# deel2.net
KiCad netlist of a schematic drawn in Altium Designer
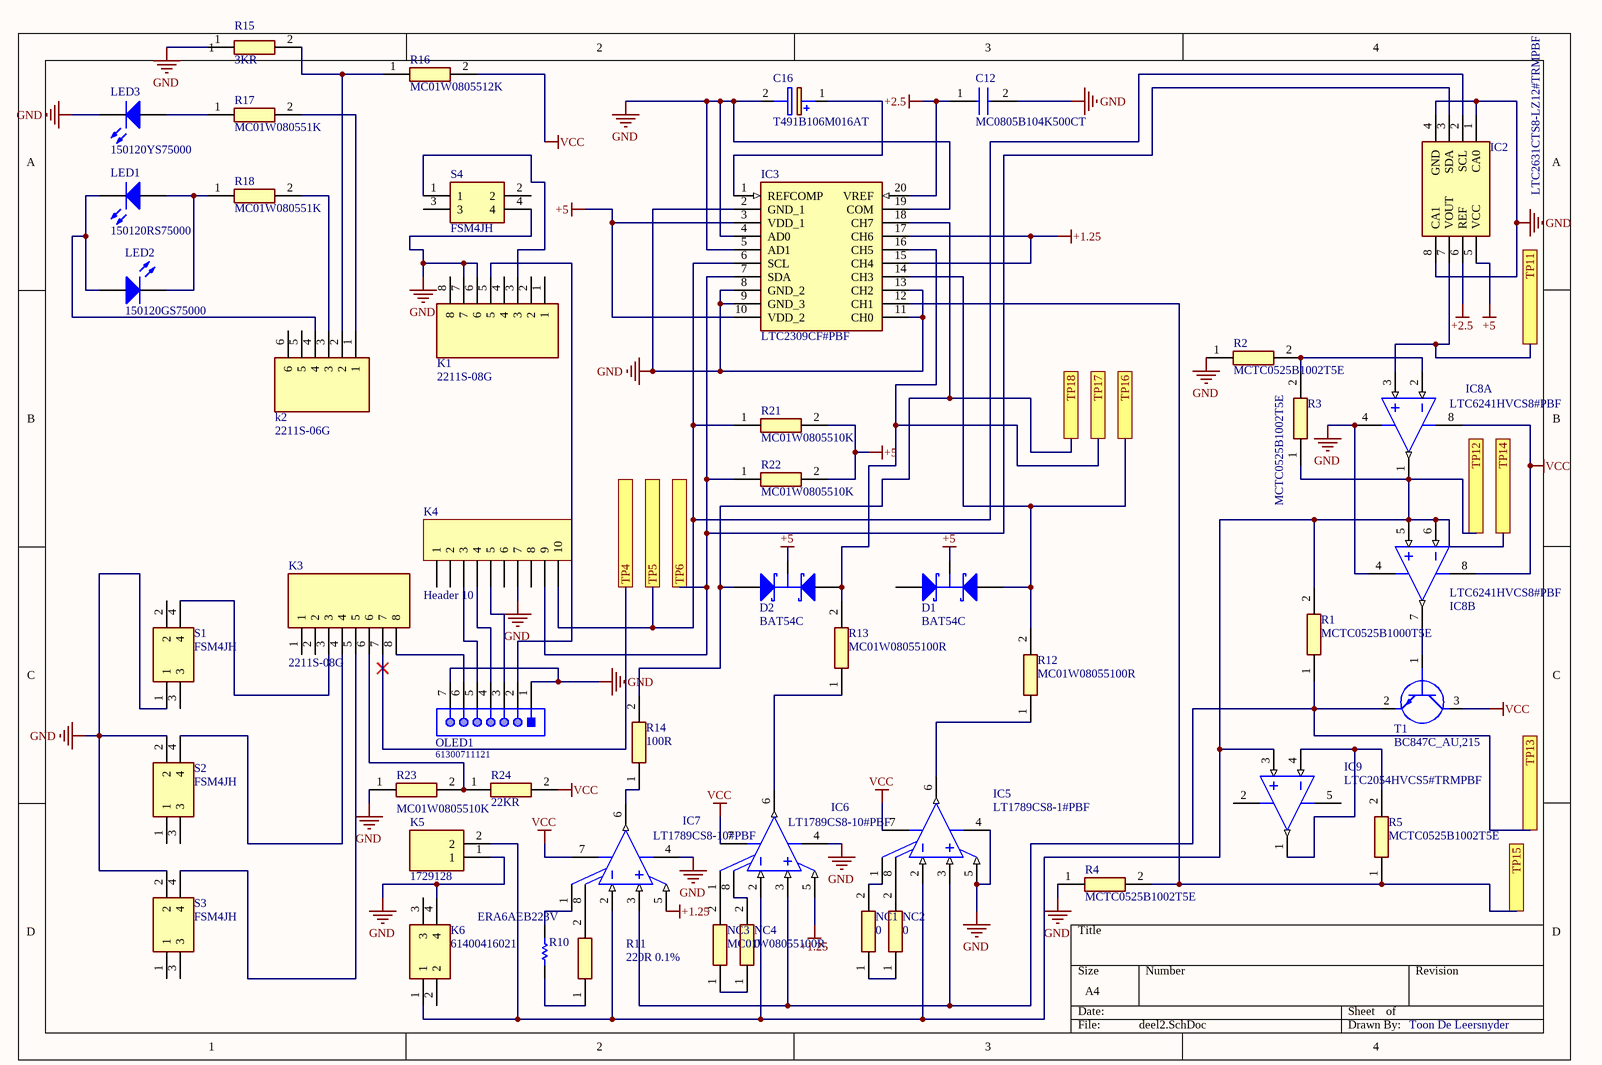
[diagram p0: deel2.SchDoc]

(export (version "E")
  (design (tool "Eeschema 10.0.6"))
  (components
    (comp (ref "C12")
      (value "MC0805B104K500CT")
      (footprint "SamacSys:CAPC2012X90N")
      (description "Capacitor")
      (libsource (lib "SamacSys") (part "MC0805B104K500CT"))
    )
    (comp (ref "C16")
      (value "T491B106M016AT")
      (footprint "SamacSys:CAPPM3528X210N")
      (description "Capacitor Polarised")
      (fields (field (name "MOUSER PART NUMBER") "80-T491B106M016"))
      (libsource (lib "SamacSys") (part "T491B106M016AT"))
    )
    (comp (ref "D1")
      (value "BAT54C")
      (footprint "NXP-SOT23-3_V")
      (description "Schottky Barrier Diode, 30 V, 2 uA, -55 to 150 degC, 3-Pin SOT23, RoHS, Tape and Reel")
      (fields (field (name "MANUFACTURER") "NXP Semiconductors"))
      (libsource (lib "Altium Content Vault") (part "NXP-DSKY_A1A2K3-3"))
    )
    (comp (ref "D2")
      (value "BAT54C")
      (footprint "NXP-SOT23-3_V")
      (description "Schottky Barrier Diode, 30 V, 2 uA, -55 to 150 degC, 3-Pin SOT23, RoHS, Tape and Reel")
      (fields (field (name "MANUFACTURER") "NXP Semiconductors"))
      (libsource (lib "Altium Content Vault") (part "NXP-DSKY_A1A2K3-3"))
    )
    (comp (ref "IC2")
      (value "LTC2631CTS8-LZ12#TRMPBF")
      (footprint "SamacSys:SOT65P280X100-8N")
      (description "Integrated Circuit")
      (fields (field (name "MOUSER PART NUMBER") "584-2631CTS8LZ12TMPF"))
      (libsource (lib "SamacSys") (part "LTC2631CTS8-LZ12#TRMPBF"))
    )
    (comp (ref "IC3")
      (value "LTC2309CF#PBF")
      (footprint "SamacSys:SOP65P640X110-20N")
      (description "Integrated Circuit")
      (fields (field (name "MOUSER PART NUMBER") "584-LTC2309CF#PBF"))
      (libsource (lib "SamacSys") (part "LTC2309CF#PBF"))
    )
    (comp (ref "IC5")
      (value "LT1789CS8-1#PBF")
      (footprint "LT-S8-8_N")
      (fields
        (field (name "MANUFACTURER") "Linear Technology")
        (field (name "LINEAR TECHNOLOGY PART NUMBER") "LT1789-1")
      )
      (libsource (lib "Altium Content Vault") (part "LT-LT1789-1-S8-8"))
    )
    (comp (ref "IC6")
      (value "LT1789CS8-10#PBF")
      (footprint "LT-S8-8_N")
      (fields
        (field (name "MANUFACTURER") "Linear Technology")
        (field (name "LINEAR TECHNOLOGY PART NUMBER") "LT1789-10")
      )
      (libsource (lib "Altium Content Vault") (part "LT-LT1789-10-S8-8"))
    )
    (comp (ref "IC7")
      (value "LT1789CS8-10#PBF")
      (footprint "LT-S8-8_N")
      (fields
        (field (name "MANUFACTURER") "Linear Technology")
        (field (name "LINEAR TECHNOLOGY PART NUMBER") "LT1789-10")
      )
      (libsource (lib "Altium Content Vault") (part "LT-LT1789-10-S8-8"))
    )
    (comp (ref "IC8")
      (value "LTC6241HVCS8#PBF")
      (footprint "LT-S8-8_M")
      (fields
        (field (name "LINEAR TECHNOLOGY PART NUMBER") "LTC6241HV")
        (field (name "MANUFACTURER") "Linear Technology")
      )
      (libsource (lib "Altium Content Vault") (part "LT-LTC6241HV-S8-8"))
    )
    (comp (ref "IC9")
      (value "LTC2054HVCS5#TRMPBF")
      (footprint "LT-S5-5-TSOT-23_N")
      (fields
        (field (name "LINEAR TECHNOLOGY PART NUMBER") "LTC2054HV")
        (field (name "MANUFACTURER") "Linear Technology")
      )
      (libsource (lib "Altium Content Vault") (part "LT-LT1395-LT18XX-LTC20XX-5"))
    )
    (comp (ref "K1")
      (value "2211S-08G")
      (footprint "SamacSys:HDRV8W64P0X254_1X8_2032X254X874P")
      (description "Connector")
      (libsource (lib "") (part "2211S-08G_1"))
    )
    (comp (ref "k2")
      (value "2211S-06G")
      (footprint "SamacSys:HDRV6W64P0X254_1X6_1524X254X1774P")
      (description "Connector")
      (libsource (lib "SamacSys") (part "2211S-06G"))
    )
    (comp (ref "K3")
      (value "2211S-08G")
      (footprint "SamacSys:HDRV8W64P0X254_1X8_2032X254X874P")
      (description "Connector")
      (libsource (lib "SamacSys") (part "2211S-08G"))
    )
    (comp (ref "K4")
      (value "Header 10")
      (footprint "HDR1X10")
      (description "Header, 10-Pin")
      (fields (field (name "PUBLISHER") "Altium Limited"))
      (libsource (lib "Miscellaneous Connectors") (part "Header 10"))
    )
    (comp (ref "K5")
      (value "1729128")
      (footprint "SamacSys:HDRV2W110P0X508_1X2_1016X810X1000P")
      (description "Connector")
      (fields (field (name "MOUSER PART NUMBER") "651-1729128"))
      (libsource (lib "SamacSys") (part "1729128"))
    )
    (comp (ref "K6")
      (value "61400416021")
      (footprint "SamacSys:USB-2.0-TYPE-A")
      (description "Connector")
      (fields (field (name "MOUSER PART NUMBER") "710-61400416021"))
      (libsource (lib "SamacSys") (part "61400416021"))
    )
    (comp (ref "LED1")
      (value "150120RS75000")
      (footprint "1206_A")
      (description "SMD mono-color Chip LED, WL-SMCW, Red")
      (fields (field (name "MANUFACTURER") "Wuerth Elektronik"))
      (libsource (lib "Altium Content Vault") (part "WE-LED_K1A2-2"))
    )
    (comp (ref "LED2")
      (value "150120GS75000")
      (footprint "1206_A")
      (description "SMD mono-color Chip LED, WL-SMCW, Green")
      (fields (field (name "MANUFACTURER") "Wuerth Elektronik"))
      (libsource (lib "Altium Content Vault") (part "WE-LED_K1A2-2"))
    )
    (comp (ref "LED3")
      (value "150120YS75000")
      (footprint "1206_A")
      (description "SMD mono-color Chip LED, WL-SMCW, Yellow")
      (fields (field (name "MANUFACTURER") "Wuerth Elektronik"))
      (libsource (lib "Altium Content Vault") (part "WE-LED_K1A2-2"))
    )
    (comp (ref "NC1")
      (value "0")
      (footprint "SamacSys:RESC2014X65N")
      (description "Resistor")
      (fields (field (name "MANUFACTURER_PART_NUMBER") "MC01W08055100R"))
      (libsource (lib "SamacSys") (part "MC01W08055100R"))
    )
    (comp (ref "NC2")
      (value "0")
      (footprint "SamacSys:RESC2014X65N")
      (description "Resistor")
      (fields (field (name "MANUFACTURER_PART_NUMBER") "MC01W08055100R"))
      (libsource (lib "SamacSys") (part "MC01W08055100R"))
    )
    (comp (ref "NC3")
      (value "MC01W08055100R")
      (footprint "SamacSys:RESC2014X65N")
      (description "Resistor")
      (libsource (lib "SamacSys") (part "MC01W08055100R"))
    )
    (comp (ref "NC4")
      (value "0")
      (footprint "SamacSys:RESC2014X65N")
      (description "Resistor")
      (fields (field (name "MANUFACTURER_PART_NUMBER") "MC01W08055100R"))
      (libsource (lib "SamacSys") (part "MC01W08055100R"))
    )
    (comp (ref "OLED1")
      (value "61300711121")
      (footprint "61300711121")
      (description "THT Vertical Pin Header WR-PHD, Pitch 2.54 mm, Single Row, 7 pins")
      (fields (field (name "MANUFACTURER") "Wurth Elektronik") (field (name "PUBLISHER") "WurthElektronik"))
      (libsource (lib "Altium Content Vault") (part "WE-CN-1P-M-R7"))
    )
    (comp (ref "R1")
      (value "MCTC0525B1000T5E")
      (footprint "SamacSys:RESC2012X65N")
      (description "Resistor")
      (libsource (lib "SamacSys") (part "MCTC0525B1000T5E"))
    )
    (comp (ref "R2")
      (value "MCTC0525B1002T5E")
      (footprint "SamacSys:RESC2012X65N")
      (description "Resistor")
      (libsource (lib "SamacSys") (part "MCTC0525B1002T5E"))
    )
    (comp (ref "R3")
      (value "MCTC0525B1002T5E")
      (footprint "SamacSys:RESC2012X65N")
      (description "Resistor")
      (libsource (lib "") (part "MCTC0525B1002T5E_1"))
    )
    (comp (ref "R4")
      (value "MCTC0525B1002T5E")
      (footprint "SamacSys:RESC2012X65N")
      (description "Resistor")
      (libsource (lib "SamacSys") (part "MCTC0525B1002T5E"))
    )
    (comp (ref "R5")
      (value "MCTC0525B1002T5E")
      (footprint "SamacSys:RESC2012X65N")
      (description "Resistor")
      (libsource (lib "") (part "MCTC0525B1002T5E_1"))
    )
    (comp (ref "R10")
      (value "ERA6AEB223V")
      (footprint "RESC2013X60X40ML20T25")
      (fields (field (name "MANUFACTURER") "Panasonic"))
      (libsource (lib "Altium Content Vault") (part "RES"))
    )
    (comp (ref "R11")
      (value "220R 0.1%")
      (footprint "SamacSys:RESC2014X65N")
      (description "Resistor")
      (fields (field (name "MANUFACTURER_PART_NUMBER") "MC01W08055100R"))
      (libsource (lib "SamacSys") (part "MC01W08055100R"))
    )
    (comp (ref "R12")
      (value "MC01W08055100R")
      (footprint "SamacSys:RESC2014X65N")
      (description "Resistor")
      (libsource (lib "SamacSys") (part "MC01W08055100R"))
    )
    (comp (ref "R13")
      (value "MC01W08055100R")
      (footprint "SamacSys:RESC2014X65N")
      (description "Resistor")
      (libsource (lib "SamacSys") (part "MC01W08055100R"))
    )
    (comp (ref "R14")
      (value "100R")
      (footprint "SamacSys:RESC2014X65N")
      (description "Resistor")
      (fields (field (name "MANUFACTURER_PART_NUMBER") "MC01W08055100R"))
      (libsource (lib "SamacSys") (part "MC01W08055100R"))
    )
    (comp (ref "R15")
      (value "3KR")
      (footprint "SamacSys:RESC2014X65N")
      (description "Resistor")
      (fields (field (name "MANUFACTURER_PART_NUMBER") "MC01W08055100R"))
      (libsource (lib "") (part "MC01W08055100R_1"))
    )
    (comp (ref "R16")
      (value "MC01W0805512K")
      (footprint "SamacSys:RESC2014X65N")
      (description "Resistor")
      (libsource (lib "SamacSys") (part "MC01W0805512K"))
    )
    (comp (ref "R17")
      (value "MC01W080551K")
      (footprint "SamacSys:RESC2014X65N")
      (description "Resistor")
      (libsource (lib "SamacSys") (part "MC01W080551K"))
    )
    (comp (ref "R18")
      (value "MC01W080551K")
      (footprint "SamacSys:RESC2014X65N")
      (description "Resistor")
      (libsource (lib "SamacSys") (part "MC01W080551K"))
    )
    (comp (ref "R21")
      (value "MC01W0805510K")
      (footprint "SamacSys:RESC2014X65N")
      (description "Resistor")
      (libsource (lib "SamacSys") (part "MC01W0805510K"))
    )
    (comp (ref "R22")
      (value "MC01W0805510K")
      (footprint "SamacSys:RESC2014X65N")
      (description "Resistor")
      (libsource (lib "SamacSys") (part "MC01W0805510K"))
    )
    (comp (ref "R23")
      (value "MC01W0805510K")
      (footprint "SamacSys:RESC2014X65N")
      (description "Resistor")
      (libsource (lib "SamacSys") (part "MC01W0805510K"))
    )
    (comp (ref "R24")
      (value "22KR")
      (footprint "SamacSys:RESC2014X65N")
      (description "Resistor")
      (fields (field (name "MANUFACTURER_PART_NUMBER") "MC01W08055100R"))
      (libsource (lib "") (part "MC01W08055100R_1"))
    )
    (comp (ref "S1")
      (value "FSM4JH")
      (footprint "SamacSys:FSM4JH")
      (description "Switch")
      (fields (field (name "MOUSER PART NUMBER") "506-FSM4JH"))
      (libsource (lib "SamacSys") (part "FSM4JH"))
    )
    (comp (ref "S2")
      (value "FSM4JH")
      (footprint "SamacSys:FSM4JH")
      (description "Switch")
      (fields (field (name "MOUSER PART NUMBER") "506-FSM4JH"))
      (libsource (lib "SamacSys") (part "FSM4JH"))
    )
    (comp (ref "S3")
      (value "FSM4JH")
      (footprint "SamacSys:FSM4JH")
      (description "Switch")
      (fields (field (name "MOUSER PART NUMBER") "506-FSM4JH"))
      (libsource (lib "SamacSys") (part "FSM4JH"))
    )
    (comp (ref "S4")
      (value "FSM4JH")
      (footprint "SamacSys:FSM4JH")
      (description "Switch")
      (fields (field (name "MOUSER PART NUMBER") "506-FSM4JH"))
      (libsource (lib "") (part "FSM4JH_1"))
    )
    (comp (ref "T1")
      (value "BC847C_AU,215")
      (footprint "SamacSys:SOT95P230X110-3N")
      (description "Transistor BJT NPN")
      (fields (field (name "MANUFACTURER_PART_NUMBER") "BC847C/AU,215"))
      (libsource (lib "SamacSys") (part "BC847C_AU,215"))
    )
  )
  (nets
    (net (code "1") (name "+1.25") (class "Default")
      (node (ref "IC3") (pin "15") (pinfunction "CH4_15") (pintype "passive"))
      (node (ref "IC3") (pin "17") (pinfunction "CH6_17") (pintype "passive"))
      (node (ref "IC6") (pin "5") (pinfunction "REF_5") (pintype "input"))
      (node (ref "IC7") (pin "5") (pinfunction "REF_5") (pintype "input"))
    )
    (net (code "2") (name "+2.5") (class "Default")
      (node (ref "C12") (pin "1") (pinfunction "1_1") (pintype "passive"))
      (node (ref "IC2") (pin "6") (pinfunction "REF_6") (pintype "passive"))
      (node (ref "IC3") (pin "20") (pinfunction "VREF_20") (pintype "input"))
    )
    (net (code "3") (name "+5") (class "Default")
      (node (ref "D1") (pin "3") (pinfunction "K_3") (pintype "passive"))
      (node (ref "D2") (pin "3") (pinfunction "K_3") (pintype "passive"))
      (node (ref "IC2") (pin "5") (pinfunction "VCC_5") (pintype "passive"))
      (node (ref "IC3") (pin "10") (pinfunction "VDD_2_10") (pintype "power_in"))
      (node (ref "IC3") (pin "3") (pinfunction "VDD_1_3") (pintype "power_in"))
      (node (ref "R21") (pin "2") (pinfunction "2_2") (pintype "passive"))
      (node (ref "R22") (pin "2") (pinfunction "2_2") (pintype "passive"))
    )
    (net (code "4") (name "/TP4") (class "Default")
      (node (ref "K3") (pin "7") (pinfunction "7_7") (pintype "passive"))
    )
    (net (code "5") (name "/TP5") (class "Default")
      (node (ref "IC2") (pin "2") (pinfunction "SCL_2") (pintype "passive"))
      (node (ref "IC3") (pin "6") (pinfunction "SCL_6") (pintype "passive"))
      (node (ref "K4") (pin "10") (pinfunction "10_10") (pintype "passive"))
      (node (ref "R21") (pin "1") (pinfunction "1_1") (pintype "passive"))
    )
    (net (code "6") (name "/TP6") (class "Default")
      (node (ref "IC2") (pin "3") (pinfunction "SDA_3") (pintype "passive"))
      (node (ref "IC3") (pin "7") (pinfunction "SDA_7") (pintype "passive"))
      (node (ref "K4") (pin "9") (pinfunction "9_9") (pintype "passive"))
      (node (ref "R22") (pin "1") (pinfunction "1_1") (pintype "passive"))
    )
    (net (code "7") (name "/TP11") (class "Default")
      (node (ref "IC2") (pin "7") (pinfunction "VOUT_7") (pintype "passive"))
      (node (ref "IC8") (pin "3") (pinfunction "+IN_A_3") (pintype "input"))
    )
    (net (code "8") (name "/TP12") (class "Default")
      (node (ref "IC5") (pin "2") (pinfunction "-IN_2") (pintype "input"))
      (node (ref "IC6") (pin "2") (pinfunction "-IN_2") (pintype "input"))
      (node (ref "IC7") (pin "2") (pinfunction "-IN_2") (pintype "input"))
      (node (ref "IC8") (pin "1") (pinfunction "OUT_A_1") (pintype "output"))
      (node (ref "IC8") (pin "5") (pinfunction "+IN_B_5") (pintype "input"))
      (node (ref "IC8") (pin "6") (pinfunction "-IN_B_6") (pintype "input"))
      (node (ref "IC9") (pin "3") (pinfunction "+IN_3") (pintype "input"))
      (node (ref "K5") (pin "2") (pinfunction "2_2") (pintype "passive"))
      (node (ref "K6") (pin "1") (pinfunction "1_1") (pintype "passive"))
      (node (ref "R1") (pin "2") (pinfunction "2_2") (pintype "passive"))
      (node (ref "R3") (pin "1") (pinfunction "1_1") (pintype "passive"))
    )
    (net (code "9") (name "/TP13") (class "Default")
      (node (ref "IC5") (pin "3") (pinfunction "+IN_3") (pintype "input"))
      (node (ref "IC6") (pin "3") (pinfunction "+IN_3") (pintype "input"))
      (node (ref "IC7") (pin "3") (pinfunction "+IN_3") (pintype "input"))
      (node (ref "R1") (pin "1") (pinfunction "1_1") (pintype "passive"))
      (node (ref "T1") (pin "2") (pinfunction "E_2") (pintype "passive"))
    )
    (net (code "10") (name "/TP15") (class "Default")
      (node (ref "IC3") (pin "12") (pinfunction "CH1_12") (pintype "passive"))
      (node (ref "R4") (pin "2") (pinfunction "2_2") (pintype "passive"))
      (node (ref "R5") (pin "1") (pinfunction "1_1") (pintype "passive"))
    )
    (net (code "11") (name "/TP16") (class "Default")
      (node (ref "D1") (pin "2") (pinfunction "A_2") (pintype "passive"))
      (node (ref "IC3") (pin "14") (pinfunction "CH3_14") (pintype "passive"))
      (node (ref "R12") (pin "2") (pinfunction "2_2") (pintype "passive"))
    )
    (net (code "12") (name "/TP17") (class "Default")
      (node (ref "D2") (pin "2") (pinfunction "A_2") (pintype "passive"))
      (node (ref "IC3") (pin "16") (pinfunction "CH5_16") (pintype "passive"))
      (node (ref "R13") (pin "2") (pinfunction "2_2") (pintype "passive"))
    )
    (net (code "13") (name "/TP18") (class "Default")
      (node (ref "D2") (pin "1") (pinfunction "A_1") (pintype "passive"))
      (node (ref "IC3") (pin "18") (pinfunction "CH7_18") (pintype "passive"))
      (node (ref "R14") (pin "2") (pinfunction "2_2") (pintype "passive"))
    )
    (net (code "14") (name "GND") (class "Default")
      (node (ref "C12") (pin "2") (pinfunction "2_2") (pintype "passive"))
      (node (ref "C16") (pin "2") (pinfunction "-_2") (pintype "passive"))
      (node (ref "IC2") (pin "1") (pinfunction "CA0_1") (pintype "passive"))
      (node (ref "IC2") (pin "4") (pinfunction "GND_4") (pintype "passive"))
      (node (ref "IC2") (pin "8") (pinfunction "CA1_8") (pintype "passive"))
      (node (ref "IC3") (pin "11") (pinfunction "CH0_11") (pintype "passive"))
      (node (ref "IC3") (pin "13") (pinfunction "CH2_13") (pintype "passive"))
      (node (ref "IC3") (pin "19") (pinfunction "COM_19") (pintype "passive"))
      (node (ref "IC3") (pin "2") (pinfunction "GND_1_2") (pintype "power_in"))
      (node (ref "IC3") (pin "4") (pinfunction "AD0_4") (pintype "passive"))
      (node (ref "IC3") (pin "5") (pinfunction "AD1_5") (pintype "passive"))
      (node (ref "IC3") (pin "8") (pinfunction "GND_2_8") (pintype "power_in"))
      (node (ref "IC3") (pin "9") (pinfunction "GND_3_9") (pintype "power_in"))
      (node (ref "IC5") (pin "4") (pinfunction "-VS_4") (pintype "power_in"))
      (node (ref "IC5") (pin "5") (pinfunction "REF_5") (pintype "input"))
      (node (ref "IC6") (pin "4") (pinfunction "-VS_4") (pintype "power_in"))
      (node (ref "IC7") (pin "4") (pinfunction "-VS_4") (pintype "power_in"))
      (node (ref "IC8") (pin "4") (pinfunction "V-_4") (pintype "power_in"))
      (node (ref "K1") (pin "6") (pinfunction "6_6") (pintype "passive"))
      (node (ref "K1") (pin "7") (pinfunction "7_7") (pintype "passive"))
      (node (ref "K4") (pin "7") (pinfunction "7_7") (pintype "passive"))
      (node (ref "K5") (pin "1") (pinfunction "1_1") (pintype "passive"))
      (node (ref "K6") (pin "4") (pinfunction "4_4") (pintype "passive"))
      (node (ref "LED3") (pin "1") (pinfunction "K_1") (pintype "passive"))
      (node (ref "OLED1") (pin "1") (pinfunction "1_1") (pintype "passive"))
      (node (ref "OLED1") (pin "7") (pinfunction "7_7") (pintype "passive"))
      (node (ref "R15") (pin "1") (pinfunction "1_1") (pintype "passive"))
      (node (ref "R2") (pin "1") (pinfunction "1_1") (pintype "passive"))
      (node (ref "R23") (pin "1") (pinfunction "1_1") (pintype "passive"))
      (node (ref "R4") (pin "1") (pinfunction "1_1") (pintype "passive"))
      (node (ref "S1") (pin "1") (pinfunction "1_1") (pintype "passive"))
      (node (ref "S2") (pin "2") (pinfunction "2_2") (pintype "passive"))
      (node (ref "S3") (pin "2") (pinfunction "2_2") (pintype "passive"))
      (node (ref "S4") (pin "4") (pinfunction "4_4") (pintype "passive"))
    )
    (net (code "15") (name "Net-(C16-+)") (class "Default")
      (node (ref "C16") (pin "1") (pinfunction "+_1") (pintype "passive"))
      (node (ref "IC3") (pin "1") (pinfunction "REFCOMP_1") (pintype "input"))
    )
    (net (code "16") (name "Net-(IC5-OUT)") (class "Default")
      (node (ref "IC5") (pin "6") (pinfunction "OUT_6") (pintype "output"))
      (node (ref "R12") (pin "1") (pinfunction "1_1") (pintype "passive"))
    )
    (net (code "17") (name "Net-(IC5-RG-Pad1)") (class "Default")
      (node (ref "IC5") (pin "1") (pinfunction "RG_1") (pintype "passive"))
      (node (ref "NC1") (pin "2") (pinfunction "2_2") (pintype "passive"))
    )
    (net (code "18") (name "Net-(IC5-RG-Pad8)") (class "Default")
      (node (ref "IC5") (pin "8") (pinfunction "RG_8") (pintype "passive"))
      (node (ref "NC2") (pin "2") (pinfunction "2_2") (pintype "passive"))
    )
    (net (code "19") (name "Net-(IC6-OUT)") (class "Default")
      (node (ref "IC6") (pin "6") (pinfunction "OUT_6") (pintype "output"))
      (node (ref "R13") (pin "1") (pinfunction "1_1") (pintype "passive"))
    )
    (net (code "20") (name "Net-(IC6-RG-Pad1)") (class "Default")
      (node (ref "IC6") (pin "1") (pinfunction "RG_1") (pintype "passive"))
      (node (ref "NC3") (pin "2") (pinfunction "2_2") (pintype "passive"))
    )
    (net (code "21") (name "Net-(IC6-RG-Pad8)") (class "Default")
      (node (ref "IC6") (pin "8") (pinfunction "RG_8") (pintype "passive"))
      (node (ref "NC4") (pin "2") (pinfunction "2_2") (pintype "passive"))
    )
    (net (code "22") (name "Net-(IC7-OUT)") (class "Default")
      (node (ref "IC7") (pin "6") (pinfunction "OUT_6") (pintype "output"))
      (node (ref "R14") (pin "1") (pinfunction "1_1") (pintype "passive"))
    )
    (net (code "23") (name "Net-(IC7-RG-Pad1)") (class "Default")
      (node (ref "IC7") (pin "1") (pinfunction "RG_1") (pintype "passive"))
      (node (ref "R10") (pin "2") (pinfunction "2_2") (pintype "passive"))
    )
    (net (code "24") (name "Net-(IC7-RG-Pad8)") (class "Default")
      (node (ref "IC7") (pin "8") (pinfunction "RG_8") (pintype "passive"))
      (node (ref "R11") (pin "2") (pinfunction "2_2") (pintype "passive"))
    )
    (net (code "25") (name "Net-(IC8A--IN_A)") (class "Default")
      (node (ref "IC8") (pin "2") (pinfunction "-IN_A_2") (pintype "input"))
      (node (ref "R2") (pin "2") (pinfunction "2_2") (pintype "passive"))
      (node (ref "R3") (pin "2") (pinfunction "2_2") (pintype "passive"))
    )
    (net (code "26") (name "Net-(IC8B-OUT_B)") (class "Default")
      (node (ref "IC8") (pin "7") (pinfunction "OUT_B_7") (pintype "output"))
      (node (ref "T1") (pin "1") (pinfunction "B_1") (pintype "passive"))
    )
    (net (code "27") (name "Net-(IC9--IN)") (class "Default")
      (node (ref "IC9") (pin "1") (pinfunction "OUT_1") (pintype "output"))
      (node (ref "IC9") (pin "4") (pinfunction "-IN_4") (pintype "input"))
      (node (ref "R5") (pin "2") (pinfunction "2_2") (pintype "passive"))
    )
    (net (code "28") (name "Net-(K1-Pad3)") (class "Default")
      (node (ref "K1") (pin "3") (pinfunction "3_3") (pintype "passive"))
      (node (ref "S4") (pin "1") (pinfunction "1_1") (pintype "passive"))
    )
    (net (code "29") (name "Net-(K1-Pad5)") (class "Default")
      (node (ref "K1") (pin "5") (pinfunction "5_5") (pintype "passive"))
      (node (ref "OLED1") (pin "2") (pinfunction "2_2") (pintype "passive"))
    )
    (net (code "30") (name "Net-(K3-Pad3)") (class "Default")
      (node (ref "K3") (pin "3") (pinfunction "3_3") (pintype "passive"))
      (node (ref "S1") (pin "4") (pinfunction "4_4") (pintype "passive"))
    )
    (net (code "31") (name "Net-(K3-Pad4)") (class "Default")
      (node (ref "K3") (pin "4") (pinfunction "4_4") (pintype "passive"))
      (node (ref "S2") (pin "4") (pinfunction "4_4") (pintype "passive"))
    )
    (net (code "32") (name "Net-(K3-Pad5)") (class "Default")
      (node (ref "K3") (pin "5") (pinfunction "5_5") (pintype "passive"))
      (node (ref "S3") (pin "4") (pinfunction "4_4") (pintype "passive"))
    )
    (net (code "33") (name "Net-(K3-Pad6)") (class "Default")
      (node (ref "K3") (pin "6") (pinfunction "6_6") (pintype "passive"))
      (node (ref "R23") (pin "2") (pinfunction "2_2") (pintype "passive"))
      (node (ref "R24") (pin "1") (pinfunction "1_1") (pintype "passive"))
    )
    (net (code "34") (name "Net-(K3-Pad8)") (class "Default")
      (node (ref "K3") (pin "8") (pinfunction "8_8") (pintype "passive"))
      (node (ref "OLED1") (pin "6") (pinfunction "6_6") (pintype "passive"))
    )
    (net (code "35") (name "Net-(K4-Pad3)") (class "Default")
      (node (ref "K4") (pin "3") (pinfunction "3_3") (pintype "passive"))
      (node (ref "OLED1") (pin "5") (pinfunction "5_5") (pintype "passive"))
    )
    (net (code "36") (name "Net-(K4-Pad4)") (class "Default")
      (node (ref "K4") (pin "4") (pinfunction "4_4") (pintype "passive"))
      (node (ref "OLED1") (pin "4") (pinfunction "4_4") (pintype "passive"))
    )
    (net (code "37") (name "Net-(K4-Pad5)") (class "Default")
      (node (ref "K4") (pin "5") (pinfunction "5_5") (pintype "passive"))
      (node (ref "OLED1") (pin "3") (pinfunction "3_3") (pintype "passive"))
    )
    (net (code "38") (name "Net-(LED1-A)") (class "Default")
      (node (ref "LED1") (pin "2") (pinfunction "A_2") (pintype "passive"))
      (node (ref "LED2") (pin "1") (pinfunction "K_1") (pintype "passive"))
      (node (ref "R18") (pin "1") (pinfunction "1_1") (pintype "passive"))
    )
    (net (code "39") (name "Net-(LED1-K)") (class "Default")
      (node (ref "LED1") (pin "1") (pinfunction "K_1") (pintype "passive"))
      (node (ref "LED2") (pin "2") (pinfunction "A_2") (pintype "passive"))
      (node (ref "k2") (pin "4") (pinfunction "4_4") (pintype "passive"))
    )
    (net (code "40") (name "Net-(LED3-A)") (class "Default")
      (node (ref "LED3") (pin "2") (pinfunction "A_2") (pintype "passive"))
      (node (ref "R17") (pin "1") (pinfunction "1_1") (pintype "passive"))
    )
    (net (code "41") (name "Net-(NC1-Pad1)") (class "Default")
      (node (ref "NC1") (pin "1") (pinfunction "1_1") (pintype "passive"))
      (node (ref "NC2") (pin "1") (pinfunction "1_1") (pintype "passive"))
    )
    (net (code "42") (name "Net-(NC3-Pad1)") (class "Default")
      (node (ref "NC3") (pin "1") (pinfunction "1_1") (pintype "passive"))
      (node (ref "NC4") (pin "1") (pinfunction "1_1") (pintype "passive"))
    )
    (net (code "43") (name "Net-(R10-Pad1)") (class "Default")
      (node (ref "R10") (pin "1") (pinfunction "1_1") (pintype "passive"))
      (node (ref "R11") (pin "1") (pinfunction "1_1") (pintype "passive"))
    )
    (net (code "44") (name "Net-(R15-Pad2)") (class "Default")
      (node (ref "R15") (pin "2") (pinfunction "2_2") (pintype "passive"))
      (node (ref "R16") (pin "1") (pinfunction "1_1") (pintype "passive"))
      (node (ref "k2") (pin "2") (pinfunction "2_2") (pintype "passive"))
    )
    (net (code "45") (name "Net-(R17-Pad2)") (class "Default")
      (node (ref "R17") (pin "2") (pinfunction "2_2") (pintype "passive"))
      (node (ref "k2") (pin "1") (pinfunction "1_1") (pintype "passive"))
    )
    (net (code "46") (name "Net-(R18-Pad2)") (class "Default")
      (node (ref "R18") (pin "2") (pinfunction "2_2") (pintype "passive"))
      (node (ref "k2") (pin "3") (pinfunction "3_3") (pintype "passive"))
    )
    (net (code "47") (name "VCC") (class "Default")
      (node (ref "IC5") (pin "7") (pinfunction "+VS_7") (pintype "power_in"))
      (node (ref "IC6") (pin "7") (pinfunction "+VS_7") (pintype "power_in"))
      (node (ref "IC7") (pin "7") (pinfunction "+VS_7") (pintype "power_in"))
      (node (ref "IC8") (pin "8") (pinfunction "V+_8") (pintype "power_in"))
      (node (ref "R16") (pin "2") (pinfunction "2_2") (pintype "passive"))
      (node (ref "R24") (pin "2") (pinfunction "2_2") (pintype "passive"))
      (node (ref "T1") (pin "3") (pinfunction "C_3") (pintype "passive"))
    )
    (net (code "48") (name "unconnected-(D1-A-Pad1)") (class "Default")
      (node (ref "D1") (pin "1") (pinfunction "A_1") (pintype "passive"))
    )
    (net (code "49") (name "unconnected-(IC9-V+-Pad5)") (class "Default")
      (node (ref "IC9") (pin "5") (pinfunction "V+_5") (pintype "power_in"))
    )
    (net (code "50") (name "unconnected-(IC9-V--Pad2)") (class "Default")
      (node (ref "IC9") (pin "2") (pinfunction "V-_2") (pintype "power_in"))
    )
    (net (code "51") (name "unconnected-(K1-Pad1)") (class "Default")
      (node (ref "K1") (pin "1") (pinfunction "1_1") (pintype "passive"))
    )
    (net (code "52") (name "unconnected-(K1-Pad2)") (class "Default")
      (node (ref "K1") (pin "2") (pinfunction "2_2") (pintype "passive"))
    )
    (net (code "53") (name "unconnected-(K1-Pad4)") (class "Default")
      (node (ref "K1") (pin "4") (pinfunction "4_4") (pintype "passive"))
    )
    (net (code "54") (name "unconnected-(K1-Pad8)") (class "Default")
      (node (ref "K1") (pin "8") (pinfunction "8_8") (pintype "passive"))
    )
    (net (code "55") (name "unconnected-(K3-Pad1)") (class "Default")
      (node (ref "K3") (pin "1") (pinfunction "1_1") (pintype "passive"))
    )
    (net (code "56") (name "unconnected-(K3-Pad2)") (class "Default")
      (node (ref "K3") (pin "2") (pinfunction "2_2") (pintype "passive"))
    )
    (net (code "57") (name "unconnected-(K4-Pad1)") (class "Default")
      (node (ref "K4") (pin "1") (pinfunction "1_1") (pintype "passive"))
    )
    (net (code "58") (name "unconnected-(K4-Pad2)") (class "Default")
      (node (ref "K4") (pin "2") (pinfunction "2_2") (pintype "passive"))
    )
    (net (code "59") (name "unconnected-(K4-Pad6)") (class "Default")
      (node (ref "K4") (pin "6") (pinfunction "6_6") (pintype "passive"))
    )
    (net (code "60") (name "unconnected-(K4-Pad8)") (class "Default")
      (node (ref "K4") (pin "8") (pinfunction "8_8") (pintype "passive"))
    )
    (net (code "61") (name "unconnected-(K6-Pad2)") (class "Default")
      (node (ref "K6") (pin "2") (pinfunction "2_2") (pintype "passive"))
    )
    (net (code "62") (name "unconnected-(K6-Pad3)") (class "Default")
      (node (ref "K6") (pin "3") (pinfunction "3_3") (pintype "passive"))
    )
    (net (code "63") (name "unconnected-(S1-Pad2)") (class "Default")
      (node (ref "S1") (pin "2") (pinfunction "2_2") (pintype "passive"))
    )
    (net (code "64") (name "unconnected-(S1-Pad3)") (class "Default")
      (node (ref "S1") (pin "3") (pinfunction "3_3") (pintype "passive"))
    )
    (net (code "65") (name "unconnected-(S2-Pad1)") (class "Default")
      (node (ref "S2") (pin "1") (pinfunction "1_1") (pintype "passive"))
    )
    (net (code "66") (name "unconnected-(S2-Pad3)") (class "Default")
      (node (ref "S2") (pin "3") (pinfunction "3_3") (pintype "passive"))
    )
    (net (code "67") (name "unconnected-(S3-Pad1)") (class "Default")
      (node (ref "S3") (pin "1") (pinfunction "1_1") (pintype "passive"))
    )
    (net (code "68") (name "unconnected-(S3-Pad3)") (class "Default")
      (node (ref "S3") (pin "3") (pinfunction "3_3") (pintype "passive"))
    )
    (net (code "69") (name "unconnected-(S4-Pad2)") (class "Default")
      (node (ref "S4") (pin "2") (pinfunction "2_2") (pintype "passive"))
    )
    (net (code "70") (name "unconnected-(S4-Pad3)") (class "Default")
      (node (ref "S4") (pin "3") (pinfunction "3_3") (pintype "passive"))
    )
    (net (code "71") (name "unconnected-(k2-Pad5)") (class "Default")
      (node (ref "k2") (pin "5") (pinfunction "5_5") (pintype "passive"))
    )
    (net (code "72") (name "unconnected-(k2-Pad6)") (class "Default")
      (node (ref "k2") (pin "6") (pinfunction "6_6") (pintype "passive"))
    )
  )
)
